# Moh2_RPi_HAT.net
KiCad netlist of a schematic drawn in EAGLE
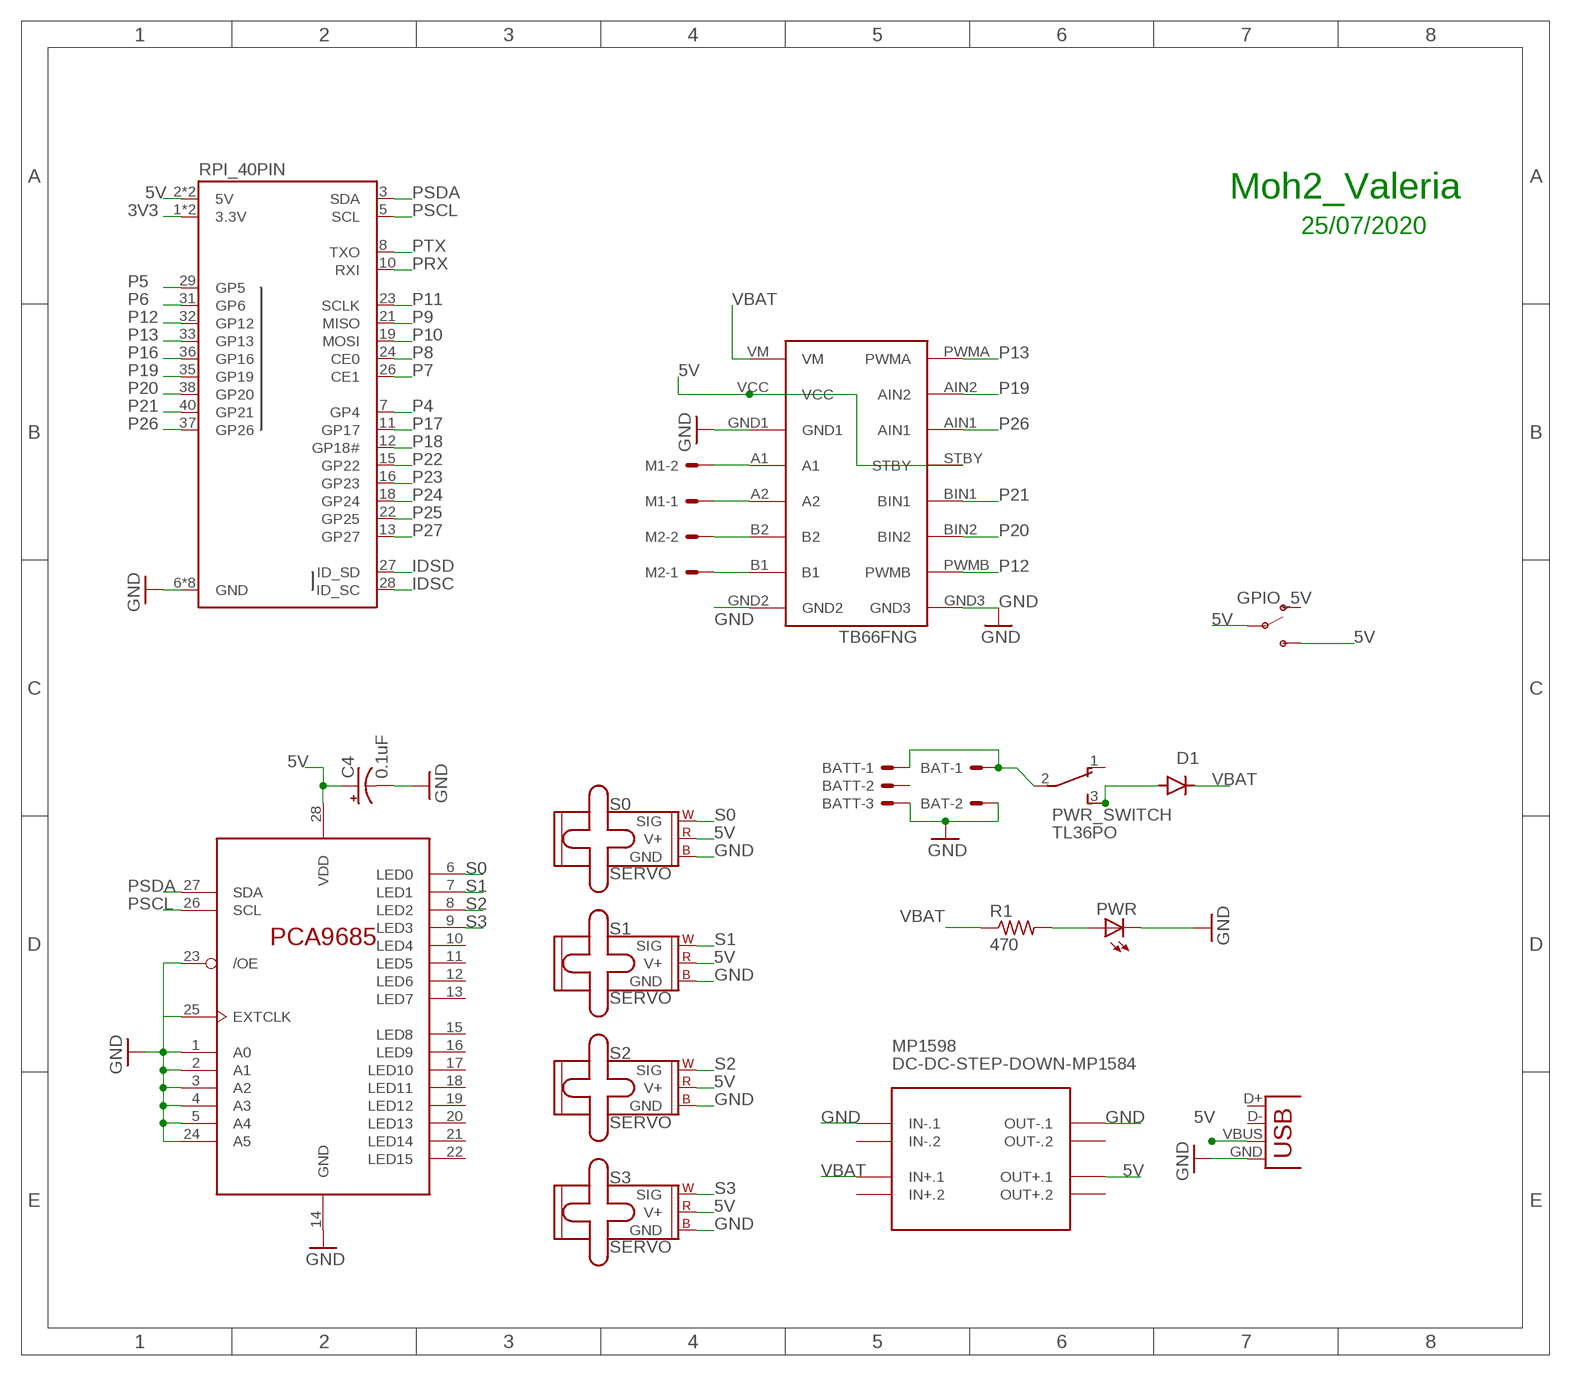
[diagram p0: schematic, sheet 1]

(export (version "E")
  (design (tool "Eeschema 10.0.6"))
  (components
    (comp (ref "BAT")
      (value "22-05-7028-02")
      (footprint "eagle-import:7395-02")
      (fields (field (name "MF") "MOLEX"))
      (libsource (lib "eagle-import") (part "22-?-0205-7028"))
    )
    (comp (ref "BATT")
      (value "22-05-7038-03")
      (footprint "eagle-import:7395-03")
      (fields (field (name "MF") "MOLEX"))
      (libsource (lib "eagle-import") (part "22-?-0305-7038"))
    )
    (comp (ref "C4")
      (value "0.1uF")
      (footprint "eagle-import:E1,8-4")
      (libsource (lib "eagle-import") (part "CPOL-USE1.8-4"))
    )
    (comp (ref "D1")
      (value "1N5400")
      (footprint "eagle-import:DO201-15")
      (libsource (lib "eagle-import") (part "1N5400"))
    )
    (comp (ref "GPIO_5V")
      (value "SWITCH-SPDT-PTH-11.6X4.0MM")
      (footprint "eagle-import:SWITCH_SPDT_PTH_11.6X4.0MM")
      (libsource (lib "eagle-import") (part "SWITCH-SPDT-PTH-11.6X4.0MM"))
    )
    (comp (ref "M1")
      (value "22-05-7028-02")
      (footprint "eagle-import:7395-02")
      (fields (field (name "MF") "MOLEX"))
      (libsource (lib "eagle-import") (part "22-?-0205-7028"))
    )
    (comp (ref "M2")
      (value "22-05-7028-02")
      (footprint "eagle-import:7395-02")
      (fields (field (name "MF") "MOLEX"))
      (libsource (lib "eagle-import") (part "22-?-0205-7028"))
    )
    (comp (ref "MP1598")
      (value "DC-DC-STEP-DOWN-MP1584")
      (footprint "eagle-import:DC-DC-STEP-DOWN-MP1584")
      (libsource (lib "eagle-import") (part "DC-DC-STEP-DOWN-MP1584"))
    )
    (comp (ref "PCA96")
      (value "PCA9685PW")
      (footprint "eagle-import:TSSOP28")
      (libsource (lib "eagle-import") (part "PCA9685PW"))
    )
    (comp (ref "PWR")
      (value "LED5MM")
      (footprint "eagle-import:LED5MM")
      (libsource (lib "eagle-import") (part "LED5MM"))
    )
    (comp (ref "PWR_SWITCH")
      (value "TL36PO")
      (footprint "eagle-import:TL3XPO")
      (libsource (lib "eagle-import") (part "TL36PO"))
    )
    (comp (ref "R1")
      (value "470")
      (footprint "eagle-import:0204_7")
      (libsource (lib "eagle-import") (part "R-US_0204/7"))
    )
    (comp (ref "RPI_40PIN")
      (value "RASPBERRYPI-40-PIN-GPIO_PTH_NO_SHROUD")
      (footprint "eagle-import:2X20")
      (libsource (lib "eagle-import") (part "RASPBERRYPI-40-PIN-GPIO_PTH_NO_SHROUD"))
    )
    (comp (ref "RPI_PWR")
      (value "USB-A-H")
      (footprint "eagle-import:USB-A-H")
      (libsource (lib "eagle-import") (part "USB-A-H"))
    )
    (comp (ref "S0")
      (value "SERVO")
      (footprint "eagle-import:1X03")
      (libsource (lib "eagle-import") (part "SERVO"))
    )
    (comp (ref "S1")
      (value "SERVO")
      (footprint "eagle-import:1X03")
      (libsource (lib "eagle-import") (part "SERVO"))
    )
    (comp (ref "S2")
      (value "SERVO")
      (footprint "eagle-import:1X03")
      (libsource (lib "eagle-import") (part "SERVO"))
    )
    (comp (ref "S3")
      (value "SERVO")
      (footprint "eagle-import:1X03")
      (libsource (lib "eagle-import") (part "SERVO"))
    )
    (comp (ref "TB66FNG")
      (value "TB6612FNG")
      (footprint "eagle-import:TB6612FNG")
      (libsource (lib "eagle-import") (part "TB6612FNG"))
    )
  )
  (nets
    (net (code "1") (name "/3V3") (class "Default")
      (node (ref "RPI_40PIN") (pin "1") (pinfunction "3.3V_1") (pintype "power_in"))
      (node (ref "RPI_40PIN") (pin "17") (pinfunction "3.3V_17") (pintype "power_in"))
    )
    (net (code "2") (name "/5V") (class "Default")
      (node (ref "C4") (pin "+") (pinfunction "+_+") (pintype "passive"))
      (node (ref "GPIO_5V") (pin "2") (pinfunction "P_2") (pintype "passive"))
      (node (ref "GPIO_5V") (pin "3") (pinfunction "S_3") (pintype "passive"))
      (node (ref "MP1598") (pin "OUT+.1") (pinfunction "OUT+.1_OUT+.1") (pintype "bidirectional"))
      (node (ref "PCA96") (pin "28") (pinfunction "VDD_28") (pintype "power_in"))
      (node (ref "RPI_40PIN") (pin "2") (pinfunction "5V_2") (pintype "power_in"))
      (node (ref "RPI_40PIN") (pin "4") (pinfunction "5V_4") (pintype "power_in"))
      (node (ref "RPI_PWR") (pin "VBUS") (pinfunction "VBUS_VBUS") (pintype "bidirectional"))
      (node (ref "S0") (pin "2") (pinfunction "V+_2") (pintype "bidirectional"))
      (node (ref "S1") (pin "2") (pinfunction "V+_2") (pintype "bidirectional"))
      (node (ref "S2") (pin "2") (pinfunction "V+_2") (pintype "bidirectional"))
      (node (ref "S3") (pin "2") (pinfunction "V+_2") (pintype "bidirectional"))
      (node (ref "TB66FNG") (pin "STBY") (pinfunction "STBY_STBY") (pintype "bidirectional"))
      (node (ref "TB66FNG") (pin "VCC") (pinfunction "VCC_VCC") (pintype "bidirectional"))
    )
    (net (code "3") (name "/IDSC") (class "Default")
      (node (ref "RPI_40PIN") (pin "28") (pinfunction "ID_SC_28") (pintype "bidirectional"))
    )
    (net (code "4") (name "/IDSD") (class "Default")
      (node (ref "RPI_40PIN") (pin "27") (pinfunction "ID_SD_27") (pintype "bidirectional"))
    )
    (net (code "5") (name "/P4") (class "Default")
      (node (ref "RPI_40PIN") (pin "7") (pinfunction "GP4_7") (pintype "bidirectional"))
    )
    (net (code "6") (name "/P5") (class "Default")
      (node (ref "RPI_40PIN") (pin "29") (pinfunction "GP5_29") (pintype "bidirectional"))
    )
    (net (code "7") (name "/P6") (class "Default")
      (node (ref "RPI_40PIN") (pin "31") (pinfunction "GP6_31") (pintype "bidirectional"))
    )
    (net (code "8") (name "/P7") (class "Default")
      (node (ref "RPI_40PIN") (pin "26") (pinfunction "CE1_26") (pintype "output"))
    )
    (net (code "9") (name "/P8") (class "Default")
      (node (ref "RPI_40PIN") (pin "24") (pinfunction "CE0_24") (pintype "output"))
    )
    (net (code "10") (name "/P9") (class "Default")
      (node (ref "RPI_40PIN") (pin "21") (pinfunction "MISO_21") (pintype "input"))
    )
    (net (code "11") (name "/P10") (class "Default")
      (node (ref "RPI_40PIN") (pin "19") (pinfunction "MOSI_19") (pintype "output"))
    )
    (net (code "12") (name "/P11") (class "Default")
      (node (ref "RPI_40PIN") (pin "23") (pinfunction "SCLK_23") (pintype "output"))
    )
    (net (code "13") (name "/P12") (class "Default")
      (node (ref "RPI_40PIN") (pin "32") (pinfunction "GP12_32") (pintype "bidirectional"))
      (node (ref "TB66FNG") (pin "PWMB") (pinfunction "PWMB_PWMB") (pintype "bidirectional"))
    )
    (net (code "14") (name "/P13") (class "Default")
      (node (ref "RPI_40PIN") (pin "33") (pinfunction "GP13_33") (pintype "bidirectional"))
      (node (ref "TB66FNG") (pin "PWMA") (pinfunction "PWMA_PWMA") (pintype "bidirectional"))
    )
    (net (code "15") (name "/P16") (class "Default")
      (node (ref "RPI_40PIN") (pin "36") (pinfunction "GP16_36") (pintype "bidirectional"))
    )
    (net (code "16") (name "/P17") (class "Default")
      (node (ref "RPI_40PIN") (pin "11") (pinfunction "GP17_11") (pintype "bidirectional"))
    )
    (net (code "17") (name "/P18") (class "Default")
      (node (ref "RPI_40PIN") (pin "12") (pinfunction "GP18#_12") (pintype "bidirectional"))
    )
    (net (code "18") (name "/P19") (class "Default")
      (node (ref "RPI_40PIN") (pin "35") (pinfunction "GP19_35") (pintype "bidirectional"))
      (node (ref "TB66FNG") (pin "AIN2") (pinfunction "AIN2_AIN2") (pintype "bidirectional"))
    )
    (net (code "19") (name "/P20") (class "Default")
      (node (ref "RPI_40PIN") (pin "38") (pinfunction "GP20_38") (pintype "bidirectional"))
      (node (ref "TB66FNG") (pin "BIN2") (pinfunction "BIN2_BIN2") (pintype "bidirectional"))
    )
    (net (code "20") (name "/P21") (class "Default")
      (node (ref "RPI_40PIN") (pin "40") (pinfunction "GP21_40") (pintype "bidirectional"))
      (node (ref "TB66FNG") (pin "BIN1") (pinfunction "BIN1_BIN1") (pintype "bidirectional"))
    )
    (net (code "21") (name "/P22") (class "Default")
      (node (ref "RPI_40PIN") (pin "15") (pinfunction "GP22_15") (pintype "bidirectional"))
    )
    (net (code "22") (name "/P23") (class "Default")
      (node (ref "RPI_40PIN") (pin "16") (pinfunction "GP23_16") (pintype "bidirectional"))
    )
    (net (code "23") (name "/P24") (class "Default")
      (node (ref "RPI_40PIN") (pin "18") (pinfunction "GP24_18") (pintype "bidirectional"))
    )
    (net (code "24") (name "/P25") (class "Default")
      (node (ref "RPI_40PIN") (pin "22") (pinfunction "GP25_22") (pintype "bidirectional"))
    )
    (net (code "25") (name "/P26") (class "Default")
      (node (ref "RPI_40PIN") (pin "37") (pinfunction "GP26_37") (pintype "bidirectional"))
      (node (ref "TB66FNG") (pin "AIN1") (pinfunction "AIN1_AIN1") (pintype "bidirectional"))
    )
    (net (code "26") (name "/P27") (class "Default")
      (node (ref "RPI_40PIN") (pin "13") (pinfunction "GP27_13") (pintype "bidirectional"))
    )
    (net (code "27") (name "/PRX") (class "Default")
      (node (ref "RPI_40PIN") (pin "10") (pinfunction "RXI_10") (pintype "input"))
    )
    (net (code "28") (name "/PSCL") (class "Default")
      (node (ref "PCA96") (pin "26") (pinfunction "SCL_26") (pintype "bidirectional"))
      (node (ref "RPI_40PIN") (pin "5") (pinfunction "SCL_5") (pintype "bidirectional"))
    )
    (net (code "29") (name "/PSDA") (class "Default")
      (node (ref "PCA96") (pin "27") (pinfunction "SDA_27") (pintype "bidirectional"))
      (node (ref "RPI_40PIN") (pin "3") (pinfunction "SDA_3") (pintype "bidirectional"))
    )
    (net (code "30") (name "/PTX") (class "Default")
      (node (ref "RPI_40PIN") (pin "8") (pinfunction "TXO_8") (pintype "output"))
    )
    (net (code "31") (name "/S0") (class "Default")
      (node (ref "PCA96") (pin "6") (pinfunction "LED0_6") (pintype "bidirectional"))
      (node (ref "S0") (pin "1") (pinfunction "SIG_1") (pintype "bidirectional"))
    )
    (net (code "32") (name "/S1") (class "Default")
      (node (ref "PCA96") (pin "7") (pinfunction "LED1_7") (pintype "bidirectional"))
      (node (ref "S1") (pin "1") (pinfunction "SIG_1") (pintype "bidirectional"))
    )
    (net (code "33") (name "/S2") (class "Default")
      (node (ref "PCA96") (pin "8") (pinfunction "LED2_8") (pintype "bidirectional"))
      (node (ref "S2") (pin "1") (pinfunction "SIG_1") (pintype "bidirectional"))
    )
    (net (code "34") (name "/S3") (class "Default")
      (node (ref "PCA96") (pin "9") (pinfunction "LED3_9") (pintype "bidirectional"))
      (node (ref "S3") (pin "1") (pinfunction "SIG_1") (pintype "bidirectional"))
    )
    (net (code "35") (name "/VBAT") (class "Default")
      (node (ref "D1") (pin "C") (pinfunction "C_C") (pintype "passive"))
      (node (ref "MP1598") (pin "IN+.1") (pinfunction "IN+.1_IN+.1") (pintype "bidirectional"))
      (node (ref "R1") (pin "1") (pinfunction "1_1") (pintype "passive"))
      (node (ref "TB66FNG") (pin "VM") (pinfunction "VM_VM") (pintype "bidirectional"))
    )
    (net (code "36") (name "GND") (class "Default")
      (node (ref "BAT") (pin "2") (pinfunction "S_2") (pintype "passive"))
      (node (ref "BATT") (pin "3") (pinfunction "S_3") (pintype "passive"))
      (node (ref "C4") (pin "-") (pinfunction "-_-") (pintype "passive"))
      (node (ref "MP1598") (pin "IN-.1") (pinfunction "IN-.1_IN-.1") (pintype "bidirectional"))
      (node (ref "MP1598") (pin "OUT-.1") (pinfunction "OUT-.1_OUT-.1") (pintype "bidirectional"))
      (node (ref "PCA96") (pin "1") (pinfunction "A0_1") (pintype "bidirectional"))
      (node (ref "PCA96") (pin "14") (pinfunction "GND_14") (pintype "power_in"))
      (node (ref "PCA96") (pin "2") (pinfunction "A1_2") (pintype "bidirectional"))
      (node (ref "PCA96") (pin "23") (pinfunction "/OE_23") (pintype "bidirectional"))
      (node (ref "PCA96") (pin "24") (pinfunction "A5_24") (pintype "bidirectional"))
      (node (ref "PCA96") (pin "25") (pinfunction "EXTCLK_25") (pintype "input"))
      (node (ref "PCA96") (pin "3") (pinfunction "A2_3") (pintype "bidirectional"))
      (node (ref "PCA96") (pin "4") (pinfunction "A3_4") (pintype "bidirectional"))
      (node (ref "PCA96") (pin "5") (pinfunction "A4_5") (pintype "bidirectional"))
      (node (ref "PWR") (pin "K") (pinfunction "C_K") (pintype "passive"))
      (node (ref "RPI_40PIN") (pin "14") (pinfunction "GND_14") (pintype "power_in"))
      (node (ref "RPI_40PIN") (pin "20") (pinfunction "GND_20") (pintype "power_in"))
      (node (ref "RPI_40PIN") (pin "25") (pinfunction "GND_25") (pintype "power_in"))
      (node (ref "RPI_40PIN") (pin "30") (pinfunction "GND_30") (pintype "power_in"))
      (node (ref "RPI_40PIN") (pin "34") (pinfunction "GND_34") (pintype "power_in"))
      (node (ref "RPI_40PIN") (pin "39") (pinfunction "GND_39") (pintype "power_in"))
      (node (ref "RPI_40PIN") (pin "6") (pinfunction "GND_6") (pintype "power_in"))
      (node (ref "RPI_40PIN") (pin "9") (pinfunction "GND_9") (pintype "power_in"))
      (node (ref "RPI_PWR") (pin "GND") (pinfunction "GND_GND") (pintype "bidirectional"))
      (node (ref "S0") (pin "3") (pinfunction "GND_3") (pintype "bidirectional"))
      (node (ref "S1") (pin "3") (pinfunction "GND_3") (pintype "bidirectional"))
      (node (ref "S2") (pin "3") (pinfunction "GND_3") (pintype "bidirectional"))
      (node (ref "S3") (pin "3") (pinfunction "GND_3") (pintype "bidirectional"))
      (node (ref "TB66FNG") (pin "GND1") (pinfunction "GND1_GND1") (pintype "bidirectional"))
      (node (ref "TB66FNG") (pin "GND2") (pinfunction "GND2_GND2") (pintype "bidirectional"))
      (node (ref "TB66FNG") (pin "GND3") (pinfunction "GND3_GND3") (pintype "bidirectional"))
    )
    (net (code "37") (name "Net-(BATA-S)") (class "Default")
      (node (ref "BAT") (pin "1") (pinfunction "S_1") (pintype "passive"))
      (node (ref "BATT") (pin "1") (pinfunction "S_1") (pintype "passive"))
      (node (ref "PWR_SWITCH") (pin "2") (pinfunction "P_2") (pintype "passive"))
    )
    (net (code "38") (name "Net-(M1A-S)") (class "Default")
      (node (ref "M1") (pin "1") (pinfunction "S_1") (pintype "passive"))
      (node (ref "TB66FNG") (pin "A2") (pinfunction "A2_A2") (pintype "bidirectional"))
    )
    (net (code "39") (name "Net-(M1B-S)") (class "Default")
      (node (ref "M1") (pin "2") (pinfunction "S_2") (pintype "passive"))
      (node (ref "TB66FNG") (pin "A1") (pinfunction "A1_A1") (pintype "bidirectional"))
    )
    (net (code "40") (name "Net-(M2A-S)") (class "Default")
      (node (ref "M2") (pin "1") (pinfunction "S_1") (pintype "passive"))
      (node (ref "TB66FNG") (pin "B1") (pinfunction "B1_B1") (pintype "bidirectional"))
    )
    (net (code "41") (name "Net-(M2B-S)") (class "Default")
      (node (ref "M2") (pin "2") (pinfunction "S_2") (pintype "passive"))
      (node (ref "TB66FNG") (pin "B2") (pinfunction "B2_B2") (pintype "bidirectional"))
    )
    (net (code "42") (name "Net-(PWR-PadA)") (class "Default")
      (node (ref "PWR") (pin "A") (pinfunction "A_A") (pintype "passive"))
      (node (ref "R1") (pin "2") (pinfunction "2_2") (pintype "passive"))
    )
    (net (code "43") (name "Net-(PWR_SWITCH-S)") (class "Default")
      (node (ref "D1") (pin "A") (pinfunction "A_A") (pintype "passive"))
      (node (ref "PWR_SWITCH") (pin "3") (pinfunction "S_3") (pintype "passive"))
    )
    (net (code "44") (name "unconnected-(BATTB-S-Pad2)") (class "Default")
      (node (ref "BATT") (pin "2") (pinfunction "S_2") (pintype "passive"))
    )
    (net (code "45") (name "unconnected-(GPIO_5V-O-Pad1)") (class "Default")
      (node (ref "GPIO_5V") (pin "1") (pinfunction "O_1") (pintype "passive"))
    )
    (net (code "46") (name "unconnected-(MP1598-PadIN+.2)") (class "Default")
      (node (ref "MP1598") (pin "IN+.2") (pinfunction "IN+.2_IN+.2") (pintype "bidirectional"))
    )
    (net (code "47") (name "unconnected-(MP1598-PadIN-.2)") (class "Default")
      (node (ref "MP1598") (pin "IN-.2") (pinfunction "IN-.2_IN-.2") (pintype "bidirectional"))
    )
    (net (code "48") (name "unconnected-(MP1598-PadOUT+.2)") (class "Default")
      (node (ref "MP1598") (pin "OUT+.2") (pinfunction "OUT+.2_OUT+.2") (pintype "bidirectional"))
    )
    (net (code "49") (name "unconnected-(MP1598-PadOUT-.2)") (class "Default")
      (node (ref "MP1598") (pin "OUT-.2") (pinfunction "OUT-.2_OUT-.2") (pintype "bidirectional"))
    )
    (net (code "50") (name "unconnected-(PCA96-LED4-Pad10)") (class "Default")
      (node (ref "PCA96") (pin "10") (pinfunction "LED4_10") (pintype "bidirectional"))
    )
    (net (code "51") (name "unconnected-(PCA96-LED5-Pad11)") (class "Default")
      (node (ref "PCA96") (pin "11") (pinfunction "LED5_11") (pintype "bidirectional"))
    )
    (net (code "52") (name "unconnected-(PCA96-LED6-Pad12)") (class "Default")
      (node (ref "PCA96") (pin "12") (pinfunction "LED6_12") (pintype "bidirectional"))
    )
    (net (code "53") (name "unconnected-(PCA96-LED7-Pad13)") (class "Default")
      (node (ref "PCA96") (pin "13") (pinfunction "LED7_13") (pintype "bidirectional"))
    )
    (net (code "54") (name "unconnected-(PCA96-LED8-Pad15)") (class "Default")
      (node (ref "PCA96") (pin "15") (pinfunction "LED8_15") (pintype "bidirectional"))
    )
    (net (code "55") (name "unconnected-(PCA96-LED9-Pad16)") (class "Default")
      (node (ref "PCA96") (pin "16") (pinfunction "LED9_16") (pintype "bidirectional"))
    )
    (net (code "56") (name "unconnected-(PCA96-LED10-Pad17)") (class "Default")
      (node (ref "PCA96") (pin "17") (pinfunction "LED10_17") (pintype "bidirectional"))
    )
    (net (code "57") (name "unconnected-(PCA96-LED11-Pad18)") (class "Default")
      (node (ref "PCA96") (pin "18") (pinfunction "LED11_18") (pintype "bidirectional"))
    )
    (net (code "58") (name "unconnected-(PCA96-LED12-Pad19)") (class "Default")
      (node (ref "PCA96") (pin "19") (pinfunction "LED12_19") (pintype "bidirectional"))
    )
    (net (code "59") (name "unconnected-(PCA96-LED13-Pad20)") (class "Default")
      (node (ref "PCA96") (pin "20") (pinfunction "LED13_20") (pintype "bidirectional"))
    )
    (net (code "60") (name "unconnected-(PCA96-LED14-Pad21)") (class "Default")
      (node (ref "PCA96") (pin "21") (pinfunction "LED14_21") (pintype "bidirectional"))
    )
    (net (code "61") (name "unconnected-(PCA96-LED15-Pad22)") (class "Default")
      (node (ref "PCA96") (pin "22") (pinfunction "LED15_22") (pintype "bidirectional"))
    )
    (net (code "62") (name "unconnected-(PWR_SWITCH-O-Pad1)") (class "Default")
      (node (ref "PWR_SWITCH") (pin "1") (pinfunction "O_1") (pintype "passive"))
    )
    (net (code "63") (name "unconnected-(RPI_PWR-PadD+)") (class "Default")
      (node (ref "RPI_PWR") (pin "D+") (pinfunction "D+_D+") (pintype "bidirectional"))
    )
    (net (code "64") (name "unconnected-(RPI_PWR-PadD-)") (class "Default")
      (node (ref "RPI_PWR") (pin "D-") (pinfunction "D-_D-") (pintype "bidirectional"))
    )
  )
)
